# Peripheral_CONNECTORS.net
KiCad netlist of a schematic drawn in Altium Designer
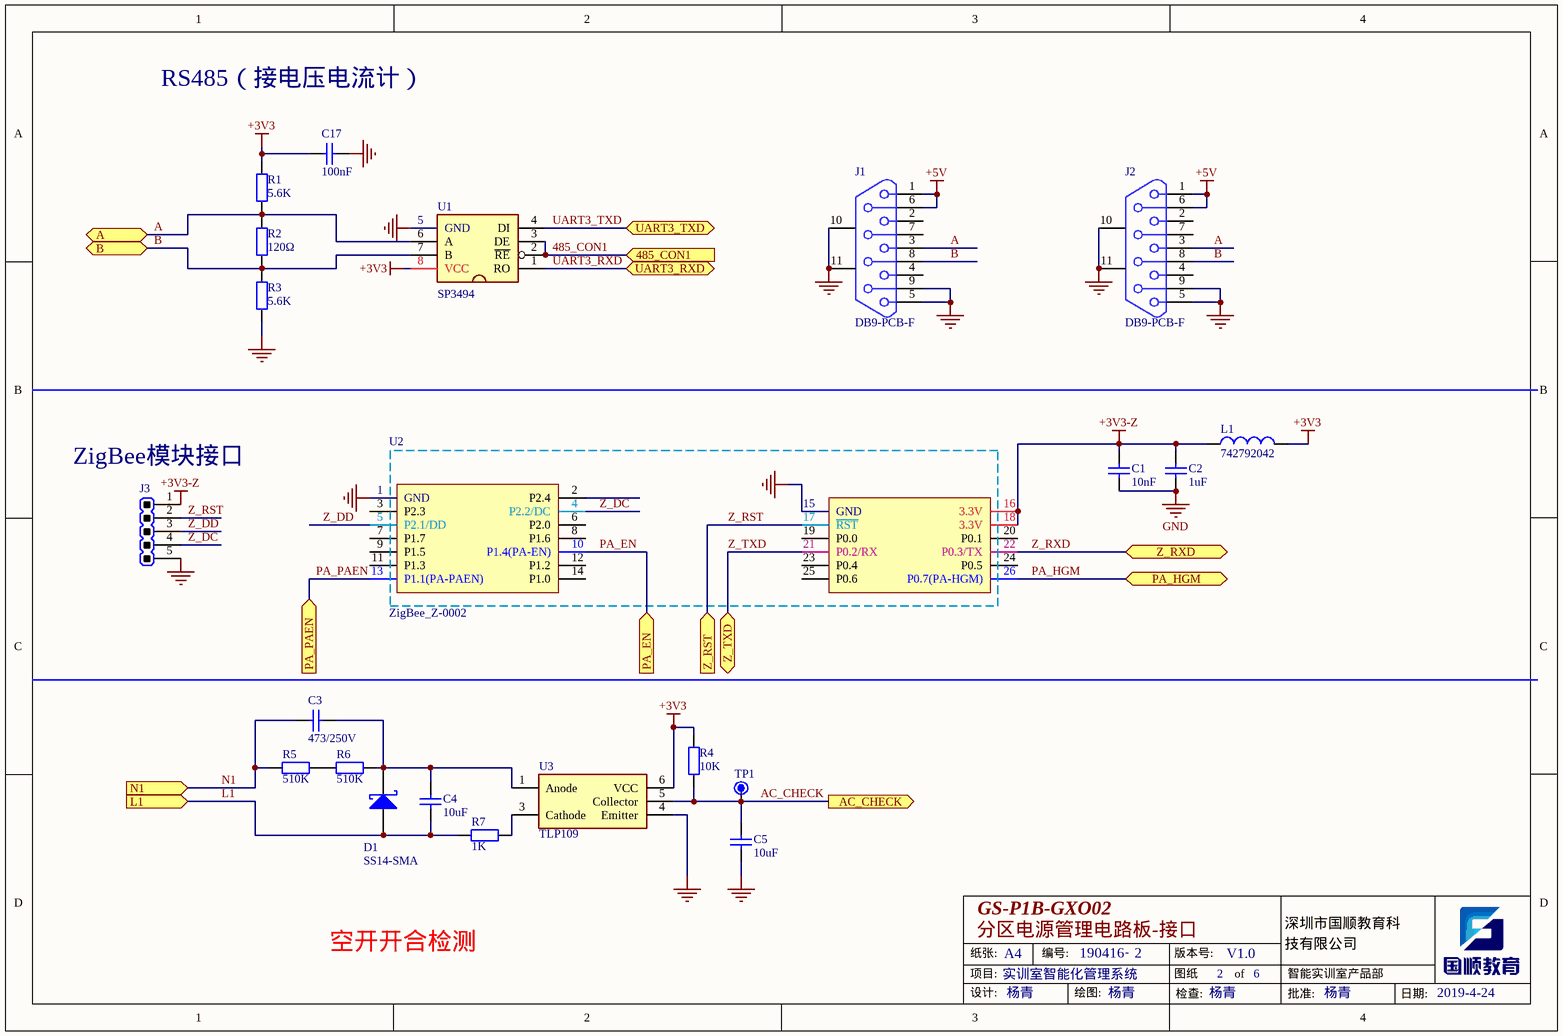
[diagram p0: Peripheral CONNECTORS.SchDoc]

(export (version "E")
  (design (tool "Eeschema 10.0.6"))
  (components
    (comp (ref "C1")
      (value "10nF")
      (footprint "C0603")
      (description "Capacitor")
      (libsource (lib "贴片电容") (part "10nF_16V_0603"))
    )
    (comp (ref "C2")
      (value "1uF")
      (footprint "C0603")
      (description "Capacitor")
      (libsource (lib "贴片电容") (part "1uF_25V_X7R_0603"))
    )
    (comp (ref "C3")
      (value "473/250V")
      (footprint "CBB-10/13X6")
      (description "CBB")
      (libsource (lib "插针电容") (part "CBB-473/250V"))
    )
    (comp (ref "C4")
      (value "10uF")
      (footprint "C0805")
      (description "CAP,10uF,106K,25V,±10%,X7R,0805")
      (libsource (lib "贴片电容") (part "10uF_25V_±10%_X7R_0805"))
    )
    (comp (ref "C5")
      (value "10uF")
      (footprint "C0603")
      (description "Capacitor")
      (libsource (lib "贴片电容") (part "10uF_16V_0603"))
    )
    (comp (ref "C17")
      (value "100nF")
      (footprint "C0603")
      (description "Capacitor")
      (libsource (lib "贴片电容") (part "100nF_50V_0603"))
    )
    (comp (ref "D1")
      (value "SS14-SMA")
      (footprint "DO-214AC/SMA/SOD106")
      (description "SS14,1A/40V,SMA")
      (libsource (lib "晶体管") (part "SS14_DO-214AC/SMA"))
    )
    (comp (ref "J1")
      (value "DB9-PCB-F")
      (footprint "DB9-PCB-F")
      (description "DB9,直插母座")
      (libsource (lib "连接器") (part "DB9-PCB-F"))
    )
    (comp (ref "J2")
      (value "DB9-PCB-F")
      (footprint "DB9-PCB-F")
      (description "DB9,直插母座")
      (libsource (lib "连接器") (part "DB9-PCB-F"))
    )
    (comp (ref "J3")
      (value "HDRM-2.54/11-1*5P-AK")
      (footprint "HDRM-2.54-1*5P-AK1")
      (description "排针,直")
      (libsource (lib "连接器") (part "HDRM-2.54/11-1*5P-AK"))
    )
    (comp (ref "L1")
      (value "742792042")
      (footprint "L0805")
      (description "WE-CBF,600@100M,500Ohm,200mA,0805,742792042")
      (libsource (lib "电感") (part "L_BEAD-742792042-0805"))
    )
    (comp (ref "R1")
      (value "5.6K")
      (footprint "R0603")
      (description "5.6K,±5%,0603")
      (libsource (lib "贴片电阻") (part "5.6K_5%_0603"))
    )
    (comp (ref "R2")
      (value "120Ω")
      (footprint "R0603")
      (description "120Ω,±5%,0603")
      (libsource (lib "贴片电阻") (part "120Ω_5%_0603"))
    )
    (comp (ref "R3")
      (value "5.6K")
      (footprint "R0603")
      (description "5.6K,±5%,0603")
      (libsource (lib "贴片电阻") (part "5.6K_5%_0603"))
    )
    (comp (ref "R4")
      (value "10K")
      (footprint "R0603")
      (description "10K,±5%,0603")
      (libsource (lib "贴片电阻") (part "10K_5%_0603"))
    )
    (comp (ref "R5") (value "510K") (footprint "R0805") (libsource (lib "贴片电阻") (part "510K_0805_5%")))
    (comp (ref "R6") (value "510K") (footprint "R0805") (libsource (lib "贴片电阻") (part "510K_0805_5%")))
    (comp (ref "R7")
      (value "1K")
      (footprint "R0805")
      (description "1K,±5%,0805")
      (libsource (lib "贴片电阻") (part "1K_5%_0805"))
    )
    (comp (ref "TP1")
      (value "TP-2.0-1P-SMD")
      (footprint "TP1-2.0/F3.0-S")
      (description "测试点")
      (libsource (lib "杂项元件") (part "TP-2.0-1P-SMD"))
    )
    (comp (ref "U1")
      (value "SP3494")
      (footprint "SOP8-1.27/4.4")
      (description "485通信芯片")
      (libsource (lib "IC") (part "SP3494_SOP8"))
    )
    (comp (ref "U2")
      (value "ZigBee_Z-0002")
      (footprint "Module_ZigBee_Z-0002")
      (description "zigbee模块")
      (libsource (lib "模块") (part "Module_ZigBee_Z-0002"))
    )
    (comp (ref "U3")
      (value "TLP109")
      (footprint "SO6-5P-1.27/3.7")
      (description "光耦")
      (libsource (lib "杂项元件") (part "OPTO_TLP109-SO6"))
    )
  )
  (nets
    (net (code "1") (name "+3V3") (class "Default")
      (node (ref "C17") (pin "1") (pinfunction "1_1") (pintype "passive"))
      (node (ref "L1") (pin "1") (pinfunction "1_1") (pintype "passive"))
      (node (ref "R1") (pin "2") (pinfunction "2_2") (pintype "passive"))
      (node (ref "R4") (pin "1") (pinfunction "1_1") (pintype "passive"))
      (node (ref "U1") (pin "8") (pinfunction "VCC_8") (pintype "passive"))
      (node (ref "U3") (pin "6") (pinfunction "VCC_6") (pintype "passive"))
    )
    (net (code "2") (name "+3V3-Z") (class "Default")
      (node (ref "C1") (pin "2") (pinfunction "2_2") (pintype "passive"))
      (node (ref "C2") (pin "1") (pinfunction "1_1") (pintype "passive"))
      (node (ref "J3") (pin "1") (pinfunction "1_1") (pintype "passive"))
      (node (ref "L1") (pin "2") (pinfunction "2_2") (pintype "passive"))
      (node (ref "U2") (pin "16") (pinfunction "3.3V_16") (pintype "passive"))
      (node (ref "U2") (pin "18") (pinfunction "3.3V_18") (pintype "passive"))
    )
    (net (code "3") (name "+5V") (class "Default")
      (node (ref "J1") (pin "1") (pinfunction "1_1") (pintype "passive"))
      (node (ref "J1") (pin "6") (pinfunction "6_6") (pintype "passive"))
      (node (ref "J2") (pin "1") (pinfunction "1_1") (pintype "passive"))
      (node (ref "J2") (pin "6") (pinfunction "6_6") (pintype "passive"))
    )
    (net (code "4") (name "/485_CON1") (class "Default")
      (node (ref "U1") (pin "2") (pinfunction "~{RE}_2") (pintype "passive"))
      (node (ref "U1") (pin "3") (pinfunction "DE_3") (pintype "passive"))
    )
    (net (code "5") (name "/A") (class "Default")
      (node (ref "J1") (pin "3") (pinfunction "3_3") (pintype "passive"))
      (node (ref "J2") (pin "3") (pinfunction "3_3") (pintype "passive"))
      (node (ref "R1") (pin "1") (pinfunction "1_1") (pintype "passive"))
      (node (ref "R2") (pin "2") (pinfunction "2_2") (pintype "passive"))
      (node (ref "U1") (pin "6") (pinfunction "A_6") (pintype "passive"))
    )
    (net (code "6") (name "/AC_CHECK") (class "Default")
      (node (ref "C5") (pin "2") (pinfunction "2_2") (pintype "passive"))
      (node (ref "R4") (pin "2") (pinfunction "2_2") (pintype "passive"))
      (node (ref "TP1") (pin "1") (pinfunction "1_1") (pintype "passive"))
      (node (ref "U3") (pin "5") (pinfunction "Collector_5") (pintype "passive"))
    )
    (net (code "7") (name "/B") (class "Default")
      (node (ref "J1") (pin "8") (pinfunction "8_8") (pintype "passive"))
      (node (ref "J2") (pin "8") (pinfunction "8_8") (pintype "passive"))
      (node (ref "R2") (pin "1") (pinfunction "1_1") (pintype "passive"))
      (node (ref "R3") (pin "2") (pinfunction "2_2") (pintype "passive"))
      (node (ref "U1") (pin "7") (pinfunction "B_7") (pintype "passive"))
    )
    (net (code "8") (name "/L1") (class "Default")
      (node (ref "C4") (pin "2") (pinfunction "2_2") (pintype "passive"))
      (node (ref "D1") (pin "1") (pinfunction "A_1") (pintype "passive"))
      (node (ref "R7") (pin "1") (pinfunction "1_1") (pintype "passive"))
    )
    (net (code "9") (name "/N1") (class "Default")
      (node (ref "C3") (pin "1") (pinfunction "1_1") (pintype "passive"))
      (node (ref "R5") (pin "1") (pinfunction "1_1") (pintype "passive"))
    )
    (net (code "10") (name "/PA_EN") (class "Default")
      (node (ref "U2") (pin "10") (pinfunction "P1.4(PA-EN)_10") (pintype "passive"))
    )
    (net (code "11") (name "/PA_HGM") (class "Default")
      (node (ref "U2") (pin "26") (pinfunction "P0.7(PA-HGM)_26") (pintype "passive"))
    )
    (net (code "12") (name "/PA_PAEN") (class "Default")
      (node (ref "U2") (pin "13") (pinfunction "P1.1(PA-PAEN)_13") (pintype "passive"))
    )
    (net (code "13") (name "/UART3_RXD") (class "Default")
      (node (ref "U1") (pin "1") (pinfunction "RO_1") (pintype "passive"))
    )
    (net (code "14") (name "/UART3_TXD") (class "Default")
      (node (ref "U1") (pin "4") (pinfunction "DI_4") (pintype "passive"))
    )
    (net (code "15") (name "/Z_DC") (class "Default")
      (node (ref "J3") (pin "4") (pinfunction "4_4") (pintype "passive"))
      (node (ref "U2") (pin "4") (pinfunction "P2.2/DC_4") (pintype "passive"))
    )
    (net (code "16") (name "/Z_DD") (class "Default")
      (node (ref "J3") (pin "3") (pinfunction "3_3") (pintype "passive"))
      (node (ref "U2") (pin "5") (pinfunction "P2.1/DD_5") (pintype "passive"))
    )
    (net (code "17") (name "/Z_RST") (class "Default")
      (node (ref "J3") (pin "2") (pinfunction "2_2") (pintype "passive"))
      (node (ref "U2") (pin "17") (pinfunction "~{RST}_17") (pintype "passive"))
    )
    (net (code "18") (name "/Z_RXD") (class "Default")
      (node (ref "U2") (pin "22") (pinfunction "P0.3/TX_22") (pintype "passive"))
    )
    (net (code "19") (name "/Z_TXD") (class "Default")
      (node (ref "U2") (pin "21") (pinfunction "P0.2/RX_21") (pintype "passive"))
    )
    (net (code "20") (name "GND") (class "Default")
      (node (ref "C1") (pin "1") (pinfunction "1_1") (pintype "passive"))
      (node (ref "C17") (pin "2") (pinfunction "2_2") (pintype "passive"))
      (node (ref "C2") (pin "2") (pinfunction "2_2") (pintype "passive"))
      (node (ref "C5") (pin "1") (pinfunction "1_1") (pintype "passive"))
      (node (ref "J1") (pin "10") (pinfunction "10_10") (pintype "passive"))
      (node (ref "J1") (pin "11") (pinfunction "11_11") (pintype "passive"))
      (node (ref "J1") (pin "5") (pinfunction "5_5") (pintype "passive"))
      (node (ref "J1") (pin "9") (pinfunction "9_9") (pintype "passive"))
      (node (ref "J2") (pin "10") (pinfunction "10_10") (pintype "passive"))
      (node (ref "J2") (pin "11") (pinfunction "11_11") (pintype "passive"))
      (node (ref "J2") (pin "5") (pinfunction "5_5") (pintype "passive"))
      (node (ref "J2") (pin "9") (pinfunction "9_9") (pintype "passive"))
      (node (ref "J3") (pin "5") (pinfunction "5_5") (pintype "passive"))
      (node (ref "R3") (pin "1") (pinfunction "1_1") (pintype "passive"))
      (node (ref "U1") (pin "5") (pinfunction "GND_5") (pintype "passive"))
      (node (ref "U2") (pin "1") (pinfunction "GND_1") (pintype "passive"))
      (node (ref "U2") (pin "15") (pinfunction "GND_15") (pintype "passive"))
      (node (ref "U3") (pin "4") (pinfunction "Emitter_4") (pintype "passive"))
    )
    (net (code "21") (name "Net-(D1-K)") (class "Default")
      (node (ref "C3") (pin "2") (pinfunction "2_2") (pintype "passive"))
      (node (ref "C4") (pin "1") (pinfunction "1_1") (pintype "passive"))
      (node (ref "D1") (pin "2") (pinfunction "K_2") (pintype "passive"))
      (node (ref "R6") (pin "2") (pinfunction "2_2") (pintype "passive"))
      (node (ref "U3") (pin "1") (pinfunction "Anode_1") (pintype "passive"))
    )
    (net (code "22") (name "Net-(R5-Pad2)") (class "Default")
      (node (ref "R5") (pin "2") (pinfunction "2_2") (pintype "passive"))
      (node (ref "R6") (pin "1") (pinfunction "1_1") (pintype "passive"))
    )
    (net (code "23") (name "Net-(U3-Cathode)") (class "Default")
      (node (ref "R7") (pin "2") (pinfunction "2_2") (pintype "passive"))
      (node (ref "U3") (pin "3") (pinfunction "Cathode_3") (pintype "passive"))
    )
    (net (code "24") (name "unconnected-(J1-Pad2)") (class "Default")
      (node (ref "J1") (pin "2") (pinfunction "2_2") (pintype "passive"))
    )
    (net (code "25") (name "unconnected-(J1-Pad4)") (class "Default")
      (node (ref "J1") (pin "4") (pinfunction "4_4") (pintype "passive"))
    )
    (net (code "26") (name "unconnected-(J1-Pad7)") (class "Default")
      (node (ref "J1") (pin "7") (pinfunction "7_7") (pintype "passive"))
    )
    (net (code "27") (name "unconnected-(J2-Pad2)") (class "Default")
      (node (ref "J2") (pin "2") (pinfunction "2_2") (pintype "passive"))
    )
    (net (code "28") (name "unconnected-(J2-Pad4)") (class "Default")
      (node (ref "J2") (pin "4") (pinfunction "4_4") (pintype "passive"))
    )
    (net (code "29") (name "unconnected-(J2-Pad7)") (class "Default")
      (node (ref "J2") (pin "7") (pinfunction "7_7") (pintype "passive"))
    )
    (net (code "30") (name "unconnected-(U2-P0.0-Pad19)") (class "Default")
      (node (ref "U2") (pin "19") (pinfunction "P0.0_19") (pintype "passive"))
    )
    (net (code "31") (name "unconnected-(U2-P0.1-Pad20)") (class "Default")
      (node (ref "U2") (pin "20") (pinfunction "P0.1_20") (pintype "passive"))
    )
    (net (code "32") (name "unconnected-(U2-P0.4-Pad23)") (class "Default")
      (node (ref "U2") (pin "23") (pinfunction "P0.4_23") (pintype "passive"))
    )
    (net (code "33") (name "unconnected-(U2-P0.5-Pad24)") (class "Default")
      (node (ref "U2") (pin "24") (pinfunction "P0.5_24") (pintype "passive"))
    )
    (net (code "34") (name "unconnected-(U2-P0.6-Pad25)") (class "Default")
      (node (ref "U2") (pin "25") (pinfunction "P0.6_25") (pintype "passive"))
    )
    (net (code "35") (name "unconnected-(U2-P1.0-Pad14)") (class "Default")
      (node (ref "U2") (pin "14") (pinfunction "P1.0_14") (pintype "passive"))
    )
    (net (code "36") (name "unconnected-(U2-P1.2-Pad12)") (class "Default")
      (node (ref "U2") (pin "12") (pinfunction "P1.2_12") (pintype "passive"))
    )
    (net (code "37") (name "unconnected-(U2-P1.3-Pad11)") (class "Default")
      (node (ref "U2") (pin "11") (pinfunction "P1.3_11") (pintype "passive"))
    )
    (net (code "38") (name "unconnected-(U2-P1.5-Pad9)") (class "Default")
      (node (ref "U2") (pin "9") (pinfunction "P1.5_9") (pintype "passive"))
    )
    (net (code "39") (name "unconnected-(U2-P1.6-Pad8)") (class "Default")
      (node (ref "U2") (pin "8") (pinfunction "P1.6_8") (pintype "passive"))
    )
    (net (code "40") (name "unconnected-(U2-P1.7-Pad7)") (class "Default")
      (node (ref "U2") (pin "7") (pinfunction "P1.7_7") (pintype "passive"))
    )
    (net (code "41") (name "unconnected-(U2-P2.0-Pad6)") (class "Default")
      (node (ref "U2") (pin "6") (pinfunction "P2.0_6") (pintype "passive"))
    )
    (net (code "42") (name "unconnected-(U2-P2.3-Pad3)") (class "Default")
      (node (ref "U2") (pin "3") (pinfunction "P2.3_3") (pintype "passive"))
    )
    (net (code "43") (name "unconnected-(U2-P2.4-Pad2)") (class "Default")
      (node (ref "U2") (pin "2") (pinfunction "P2.4_2") (pintype "passive"))
    )
  )
)
